# Adafruit_USB_C_microlipo_charger.net
KiCad netlist of a schematic drawn in EAGLE
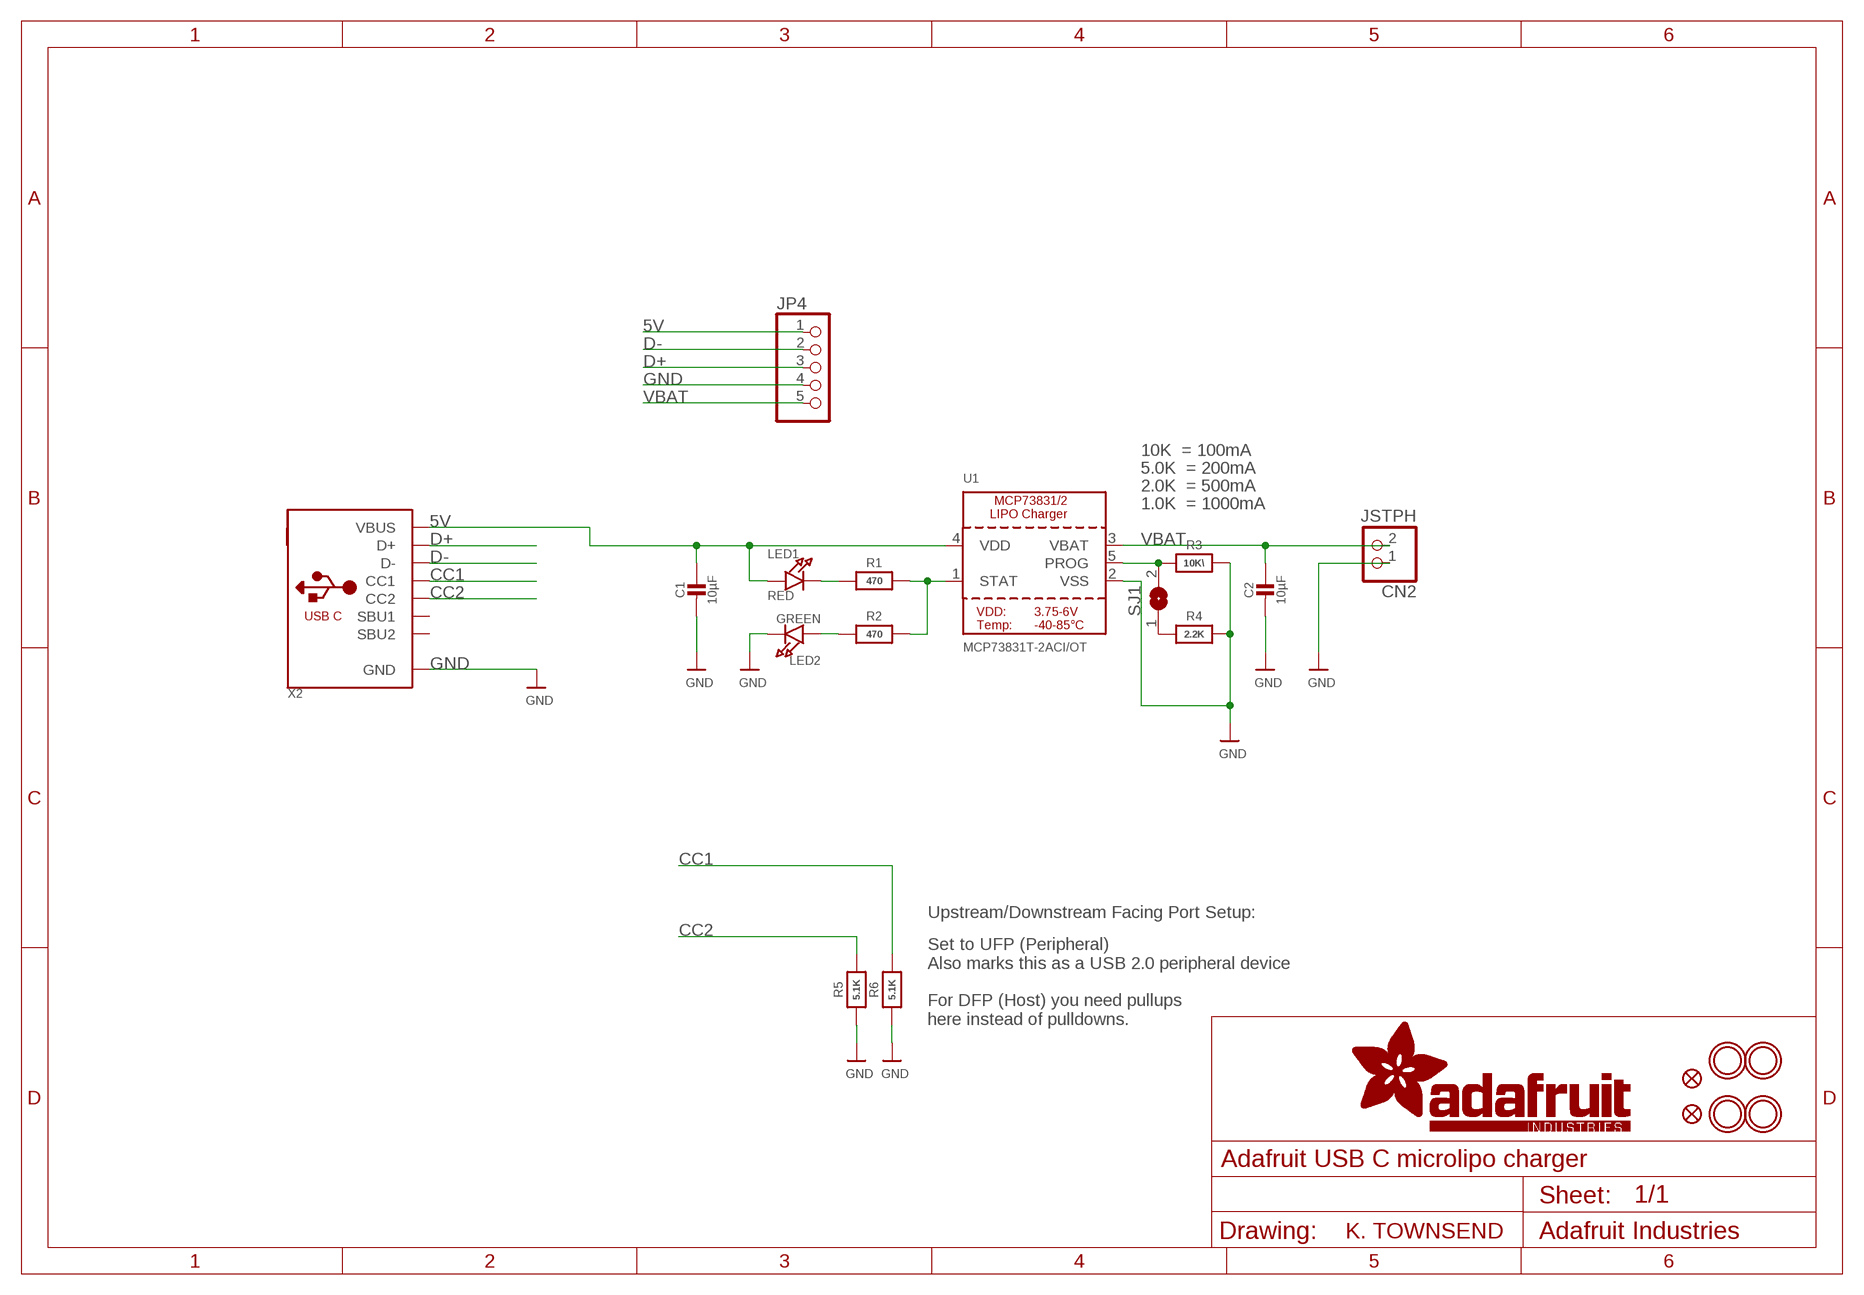
[diagram p0: schematic, sheet 1]

(export (version "E")
  (design (tool "Eeschema 10.0.6"))
  (components
    (comp (ref "C1")
      (value "10µF")
      (footprint "eagle-import:0805-NO@1")
      (libsource (lib "eagle-import") (part "CAP_CERAMIC0805-NOOUTLINE"))
    )
    (comp (ref "C2")
      (value "10µF")
      (footprint "eagle-import:0805-NO@1")
      (libsource (lib "eagle-import") (part "CAP_CERAMIC0805-NOOUTLINE"))
    )
    (comp (ref "CN2")
      (value "JSTPH")
      (footprint "eagle-import:JSTPH2")
      (libsource (lib "eagle-import") (part "JST_2PIN"))
    )
    (comp (ref "FID1")
      (value "FIDUCIAL\"\"")
      (footprint "eagle-import:FIDUCIAL_1MM")
      (libsource (lib "eagle-import") (part "FIDUCIAL{dblquote}{dblquote}"))
    )
    (comp (ref "FID2")
      (value "FIDUCIAL\"\"")
      (footprint "eagle-import:FIDUCIAL_1MM")
      (fields (field (name "BOM") "EXCLUDE"))
      (libsource (lib "eagle-import") (part "FIDUCIAL{dblquote}{dblquote}"))
    )
    (comp (ref "JP4")
      (value "HEADER-1X570MIL")
      (footprint "eagle-import:1X05_ROUND_70")
      (libsource (lib "eagle-import") (part "HEADER-1X570MIL"))
    )
    (comp (ref "LED1")
      (value "RED")
      (footprint "eagle-import:CHIPLED_0805_NOOUTLINE")
      (libsource (lib "eagle-import") (part "LED0805_NOOUTLINE"))
    )
    (comp (ref "LED2")
      (value "GREEN")
      (footprint "eagle-import:CHIPLED_0805_NOOUTLINE")
      (libsource (lib "eagle-import") (part "LED0805_NOOUTLINE"))
    )
    (comp (ref "R1")
      (value "470")
      (footprint "eagle-import:0603-NO")
      (libsource (lib "eagle-import") (part "RESISTOR_0603_NOOUT"))
    )
    (comp (ref "R2")
      (value "470")
      (footprint "eagle-import:0603-NO")
      (libsource (lib "eagle-import") (part "RESISTOR_0603_NOOUT"))
    )
    (comp (ref "R3")
      (value "10K\\")
      (footprint "eagle-import:0603-NO")
      (libsource (lib "eagle-import") (part "RESISTOR_0603_NOOUT"))
    )
    (comp (ref "R4")
      (value "2.2K")
      (footprint "eagle-import:0603-NO")
      (libsource (lib "eagle-import") (part "RESISTOR_0603_NOOUT"))
    )
    (comp (ref "R5")
      (value "5.1K")
      (footprint "eagle-import:0603-NO")
      (libsource (lib "eagle-import") (part "RESISTOR_0603_NOOUT"))
    )
    (comp (ref "R6")
      (value "5.1K")
      (footprint "eagle-import:0603-NO")
      (libsource (lib "eagle-import") (part "RESISTOR_0603_NOOUT"))
    )
    (comp (ref "SJ1")
      (value "SOLDERJUMPER")
      (footprint "eagle-import:SOLDERJUMPER_ARROW_NOPASTE")
      (libsource (lib "eagle-import") (part "SOLDERJUMPER"))
    )
    (comp (ref "U$9")
      (value "MOUNTINGHOLE2.5")
      (footprint "eagle-import:MOUNTINGHOLE_2.5_PLATED")
      (libsource (lib "eagle-import") (part "MOUNTINGHOLE2.5"))
    )
    (comp (ref "U$10")
      (value "MOUNTINGHOLE2.5")
      (footprint "eagle-import:MOUNTINGHOLE_2.5_PLATED")
      (libsource (lib "eagle-import") (part "MOUNTINGHOLE2.5"))
    )
    (comp (ref "U$11")
      (value "MOUNTINGHOLE2.5")
      (footprint "eagle-import:MOUNTINGHOLE_2.5_PLATED")
      (libsource (lib "eagle-import") (part "MOUNTINGHOLE2.5"))
    )
    (comp (ref "U$12")
      (value "MOUNTINGHOLE2.5")
      (footprint "eagle-import:MOUNTINGHOLE_2.5_PLATED")
      (libsource (lib "eagle-import") (part "MOUNTINGHOLE2.5"))
    )
    (comp (ref "U1")
      (value "MCP73831T-2ACI/OT")
      (footprint "eagle-import:SOT23-5")
      (libsource (lib "eagle-import") (part "MCP73831/2"))
    )
    (comp (ref "X2")
      (value "USB_C")
      (footprint "eagle-import:USB_C_CUSB31-CFM2AX-01-X")
      (libsource (lib "eagle-import") (part "USB_C"))
    )
  )
  (nets
    (net (code "1") (name "/5V") (class "Default")
      (node (ref "C1") (pin "1") (pinfunction "1_1") (pintype "passive"))
      (node (ref "JP4") (pin "1") (pinfunction "1_1") (pintype "passive"))
      (node (ref "LED1") (pin "A") (pinfunction "A_A") (pintype "passive"))
      (node (ref "U1") (pin "4") (pinfunction "VDD_4") (pintype "power_in"))
      (node (ref "X2") (pin "A4B9") (pinfunction "VBUS_A4B9") (pintype "power_in"))
      (node (ref "X2") (pin "B4A9") (pinfunction "VBUS_B4A9") (pintype "power_in"))
    )
    (net (code "2") (name "/CC1") (class "Default")
      (node (ref "R6") (pin "2") (pinfunction "2_2") (pintype "passive"))
      (node (ref "X2") (pin "A5") (pinfunction "CC1_A5") (pintype "bidirectional"))
    )
    (net (code "3") (name "/CC2") (class "Default")
      (node (ref "R5") (pin "2") (pinfunction "2_2") (pintype "passive"))
      (node (ref "X2") (pin "B5") (pinfunction "CC2_B5") (pintype "bidirectional"))
    )
    (net (code "4") (name "/D+") (class "Default")
      (node (ref "JP4") (pin "3") (pinfunction "3_3") (pintype "passive"))
      (node (ref "X2") (pin "A6") (pinfunction "D+_A6") (pintype "bidirectional"))
      (node (ref "X2") (pin "B6") (pinfunction "D+_B6") (pintype "bidirectional"))
    )
    (net (code "5") (name "/D-") (class "Default")
      (node (ref "JP4") (pin "2") (pinfunction "2_2") (pintype "passive"))
      (node (ref "X2") (pin "A7") (pinfunction "D-_A7") (pintype "bidirectional"))
      (node (ref "X2") (pin "B7") (pinfunction "D-_B7") (pintype "bidirectional"))
    )
    (net (code "6") (name "/VBAT") (class "Default")
      (node (ref "C2") (pin "1") (pinfunction "1_1") (pintype "passive"))
      (node (ref "CN2") (pin "2") (pinfunction "2_2") (pintype "passive"))
      (node (ref "JP4") (pin "5") (pinfunction "5_5") (pintype "passive"))
      (node (ref "U1") (pin "3") (pinfunction "VBAT_3") (pintype "power_in"))
    )
    (net (code "7") (name "GND") (class "Default")
      (node (ref "C1") (pin "2") (pinfunction "2_2") (pintype "passive"))
      (node (ref "C2") (pin "2") (pinfunction "2_2") (pintype "passive"))
      (node (ref "CN2") (pin "1") (pinfunction "1_1") (pintype "passive"))
      (node (ref "JP4") (pin "4") (pinfunction "4_4") (pintype "passive"))
      (node (ref "LED2") (pin "C") (pinfunction "C_C") (pintype "passive"))
      (node (ref "R3") (pin "2") (pinfunction "2_2") (pintype "passive"))
      (node (ref "R4") (pin "2") (pinfunction "2_2") (pintype "passive"))
      (node (ref "R5") (pin "1") (pinfunction "1_1") (pintype "passive"))
      (node (ref "R6") (pin "1") (pinfunction "1_1") (pintype "passive"))
      (node (ref "U1") (pin "2") (pinfunction "VSS_2") (pintype "power_in"))
      (node (ref "X2") (pin "A1B12") (pinfunction "GND_A1B12") (pintype "power_in"))
      (node (ref "X2") (pin "B1A12") (pinfunction "GND_B1A12") (pintype "power_in"))
    )
    (net (code "8") (name "Net-(LED1-PadC)") (class "Default")
      (node (ref "LED1") (pin "C") (pinfunction "C_C") (pintype "passive"))
      (node (ref "R1") (pin "1") (pinfunction "1_1") (pintype "passive"))
    )
    (net (code "9") (name "Net-(LED2-PadA)") (class "Default")
      (node (ref "LED2") (pin "A") (pinfunction "A_A") (pintype "passive"))
      (node (ref "R2") (pin "1") (pinfunction "1_1") (pintype "passive"))
    )
    (net (code "10") (name "Net-(R4-Pad1)") (class "Default")
      (node (ref "R4") (pin "1") (pinfunction "1_1") (pintype "passive"))
      (node (ref "SJ1") (pin "1") (pinfunction "1_1") (pintype "passive"))
    )
    (net (code "11") (name "Net-(U1-PROG)") (class "Default")
      (node (ref "R3") (pin "1") (pinfunction "1_1") (pintype "passive"))
      (node (ref "SJ1") (pin "2") (pinfunction "2_2") (pintype "passive"))
      (node (ref "U1") (pin "5") (pinfunction "PROG_5") (pintype "input"))
    )
    (net (code "12") (name "Net-(U1-STAT)") (class "Default")
      (node (ref "R1") (pin "2") (pinfunction "2_2") (pintype "passive"))
      (node (ref "R2") (pin "2") (pinfunction "2_2") (pintype "passive"))
      (node (ref "U1") (pin "1") (pinfunction "STAT_1") (pintype "output"))
    )
    (net (code "13") (name "unconnected-(X2-SBU1-PadA8)") (class "Default")
      (node (ref "X2") (pin "A8") (pinfunction "SBU1_A8") (pintype "bidirectional"))
    )
    (net (code "14") (name "unconnected-(X2-SBU2-PadB8)") (class "Default")
      (node (ref "X2") (pin "B8") (pinfunction "SBU2_B8") (pintype "bidirectional"))
    )
  )
)
